# ESPWaterMeter.net
KiCad netlist of a schematic drawn in EAGLE
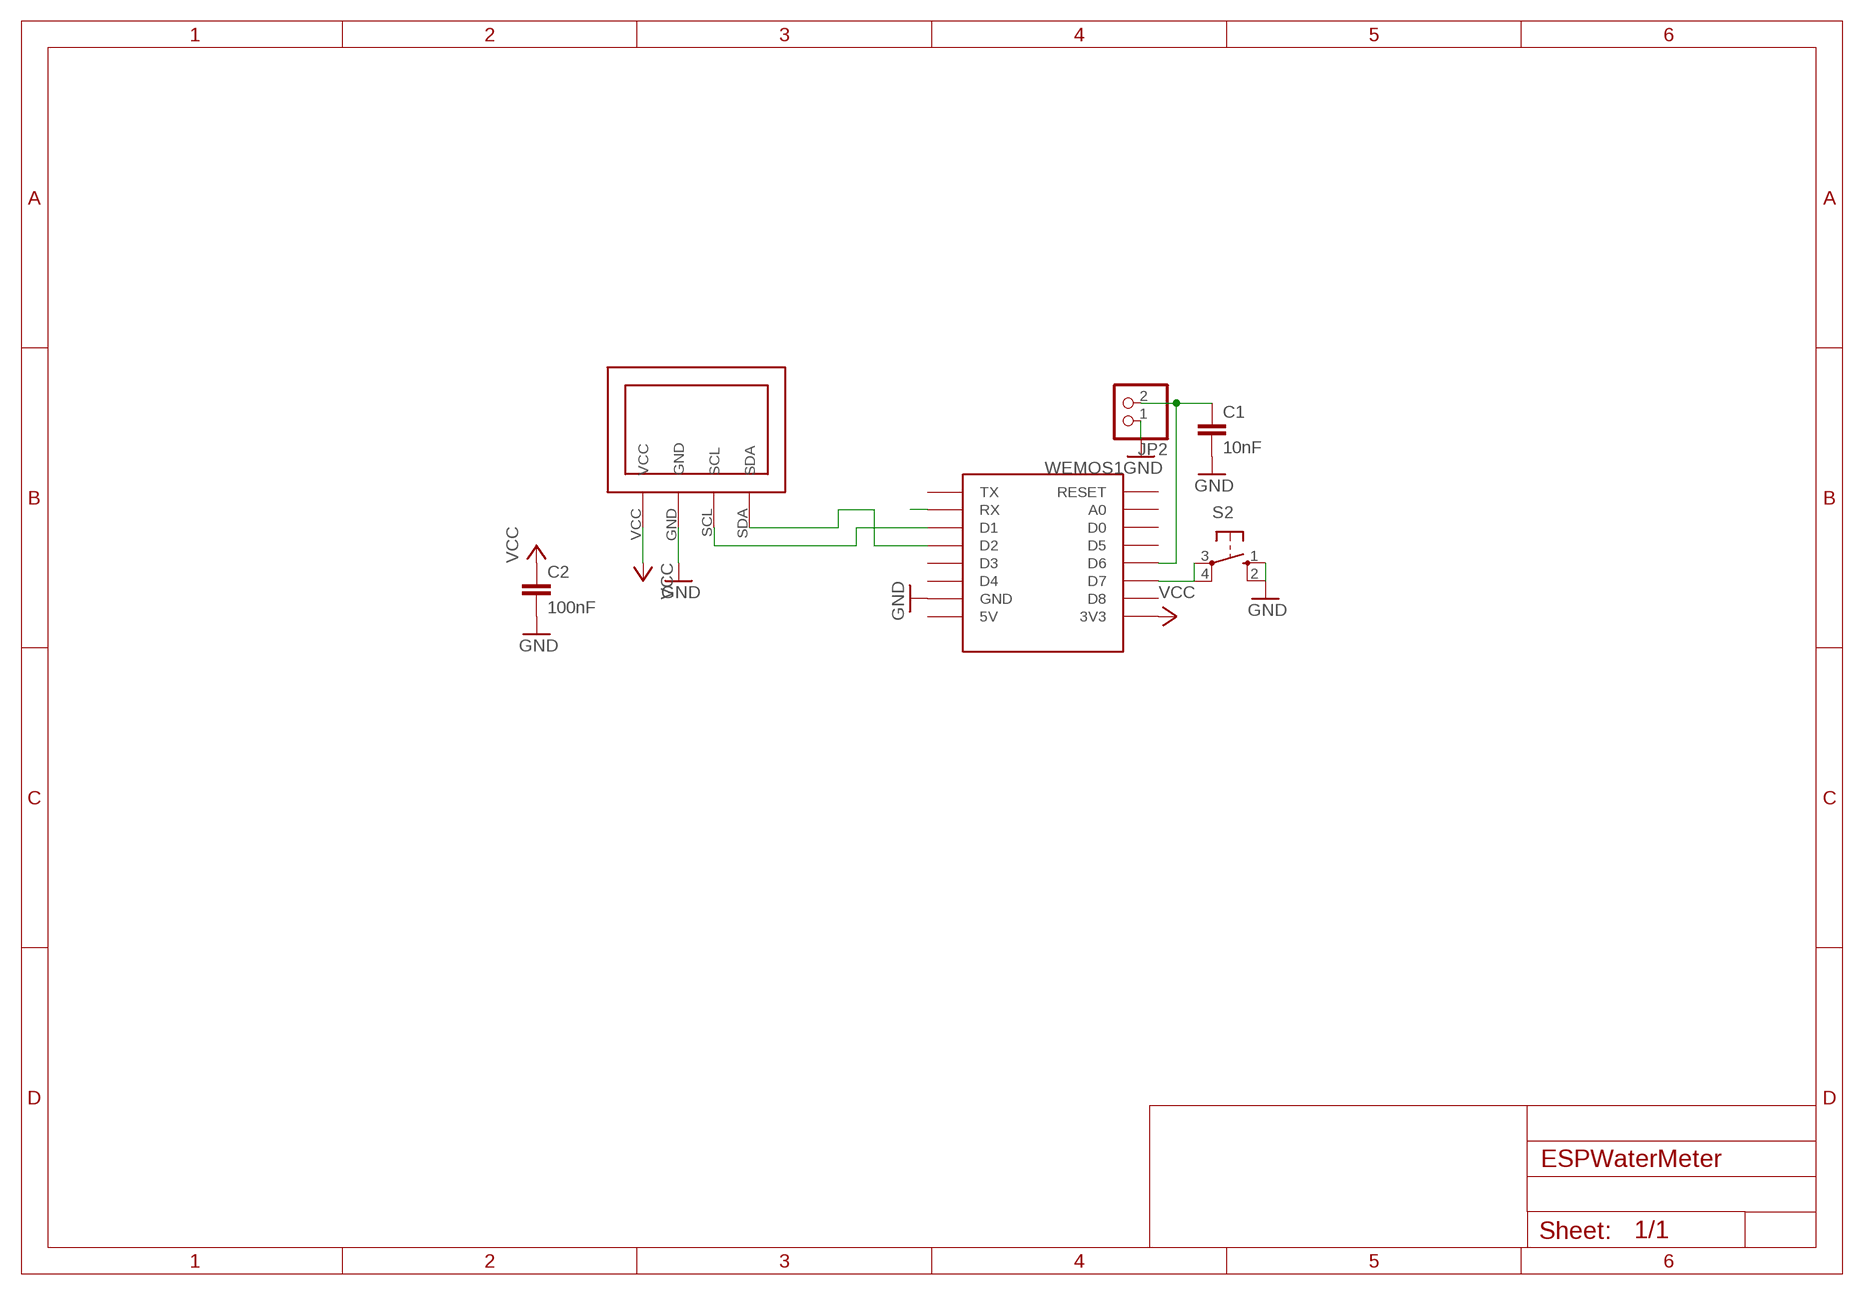
[diagram p0: schematic, sheet 1]

(export (version "E")
  (design (tool "Eeschema 10.0.6"))
  (components
    (comp (ref "C1")
      (value "10nF")
      (footprint "eagle-import:C025-025X050")
      (libsource (lib "eagle-import") (part "C-EU025-025X050"))
    )
    (comp (ref "C2")
      (value "100nF")
      (footprint "eagle-import:C025-025X050")
      (libsource (lib "eagle-import") (part "C-EU025-025X050"))
    )
    (comp (ref "JP2")
      (value "PINHD-1X2")
      (footprint "eagle-import:1X02")
      (libsource (lib "eagle-import") (part "PINHD-1X2"))
    )
    (comp (ref "S2")
      (value "10-XX")
      (footprint "eagle-import:B3F-10XX")
      (fields (field (name "MPN") "B3F-1000"))
      (libsource (lib "eagle-import") (part "10-XX"))
    )
    (comp (ref "U$2")
      (value "OLED128X64")
      (footprint "eagle-import:OLED128X64")
      (libsource (lib "eagle-import") (part "OLED128X64"))
    )
    (comp (ref "WEMOS1")
      (value "WEMOS-D1-MINI")
      (footprint "eagle-import:WEMOS-D1-MINI")
      (libsource (lib "eagle-import") (part "WEMOS-D1-MINI"))
    )
  )
  (nets
    (net (code "1") (name "GND") (class "Default")
      (node (ref "C1") (pin "2") (pinfunction "2_2") (pintype "passive"))
      (node (ref "C2") (pin "2") (pinfunction "2_2") (pintype "passive"))
      (node (ref "JP2") (pin "1") (pinfunction "1_1") (pintype "passive"))
      (node (ref "S2") (pin "1") (pinfunction "S_1") (pintype "passive"))
      (node (ref "S2") (pin "2") (pinfunction "S1_2") (pintype "passive"))
      (node (ref "U$2") (pin "GND") (pinfunction "GND_GND") (pintype "bidirectional"))
      (node (ref "WEMOS1") (pin "GND") (pinfunction "GND_GND") (pintype "bidirectional"))
    )
    (net (code "2") (name "Net-(C1-Pad1)") (class "Default")
      (node (ref "C1") (pin "1") (pinfunction "1_1") (pintype "passive"))
      (node (ref "JP2") (pin "2") (pinfunction "2_2") (pintype "passive"))
      (node (ref "WEMOS1") (pin "D6") (pinfunction "D6_D6") (pintype "bidirectional"))
    )
    (net (code "3") (name "Net-(S2-P)") (class "Default")
      (node (ref "S2") (pin "3") (pinfunction "P_3") (pintype "passive"))
      (node (ref "S2") (pin "4") (pinfunction "P1_4") (pintype "passive"))
      (node (ref "WEMOS1") (pin "D7") (pinfunction "D7_D7") (pintype "bidirectional"))
    )
    (net (code "4") (name "Net-(U$2-PadSCL)") (class "Default")
      (node (ref "U$2") (pin "SCL") (pinfunction "SCL_SCL") (pintype "bidirectional"))
      (node (ref "WEMOS1") (pin "D1") (pinfunction "D1_D1") (pintype "bidirectional"))
    )
    (net (code "5") (name "Net-(U$2-PadSDA)") (class "Default")
      (node (ref "U$2") (pin "SDA") (pinfunction "SDA_SDA") (pintype "bidirectional"))
      (node (ref "WEMOS1") (pin "D2") (pinfunction "D2_D2") (pintype "bidirectional"))
    )
    (net (code "6") (name "VCC") (class "Default")
      (node (ref "C2") (pin "1") (pinfunction "1_1") (pintype "passive"))
      (node (ref "U$2") (pin "VCC") (pinfunction "VCC_VCC") (pintype "bidirectional"))
      (node (ref "WEMOS1") (pin "3V3") (pinfunction "3V3_3V3") (pintype "bidirectional"))
    )
    (net (code "7") (name "unconnected-(WEMOS1-Pad5V)") (class "Default")
      (node (ref "WEMOS1") (pin "5V") (pinfunction "5V_5V") (pintype "bidirectional"))
    )
    (net (code "8") (name "unconnected-(WEMOS1-PadA0)") (class "Default")
      (node (ref "WEMOS1") (pin "A0") (pinfunction "A0_A0") (pintype "bidirectional"))
    )
    (net (code "9") (name "unconnected-(WEMOS1-PadD0)") (class "Default")
      (node (ref "WEMOS1") (pin "D0") (pinfunction "D0_D0") (pintype "bidirectional"))
    )
    (net (code "10") (name "unconnected-(WEMOS1-PadD3)") (class "Default")
      (node (ref "WEMOS1") (pin "D3") (pinfunction "D3_D3") (pintype "bidirectional"))
    )
    (net (code "11") (name "unconnected-(WEMOS1-PadD4)") (class "Default")
      (node (ref "WEMOS1") (pin "D4") (pinfunction "D4_D4") (pintype "bidirectional"))
    )
    (net (code "12") (name "unconnected-(WEMOS1-PadD5)") (class "Default")
      (node (ref "WEMOS1") (pin "D5") (pinfunction "D5_D5") (pintype "bidirectional"))
    )
    (net (code "13") (name "unconnected-(WEMOS1-PadD8)") (class "Default")
      (node (ref "WEMOS1") (pin "D8") (pinfunction "D8_D8") (pintype "bidirectional"))
    )
    (net (code "14") (name "unconnected-(WEMOS1-PadRESET)") (class "Default")
      (node (ref "WEMOS1") (pin "RESET") (pinfunction "RESET_RESET") (pintype "bidirectional"))
    )
    (net (code "15") (name "unconnected-(WEMOS1-PadRX)") (class "Default")
      (node (ref "WEMOS1") (pin "RX") (pinfunction "RX_RX") (pintype "bidirectional"))
    )
    (net (code "16") (name "unconnected-(WEMOS1-PadTX)") (class "Default")
      (node (ref "WEMOS1") (pin "TX") (pinfunction "TX_TX") (pintype "bidirectional"))
    )
  )
)
